# v2.net
KiCad netlist of a schematic drawn in EAGLE
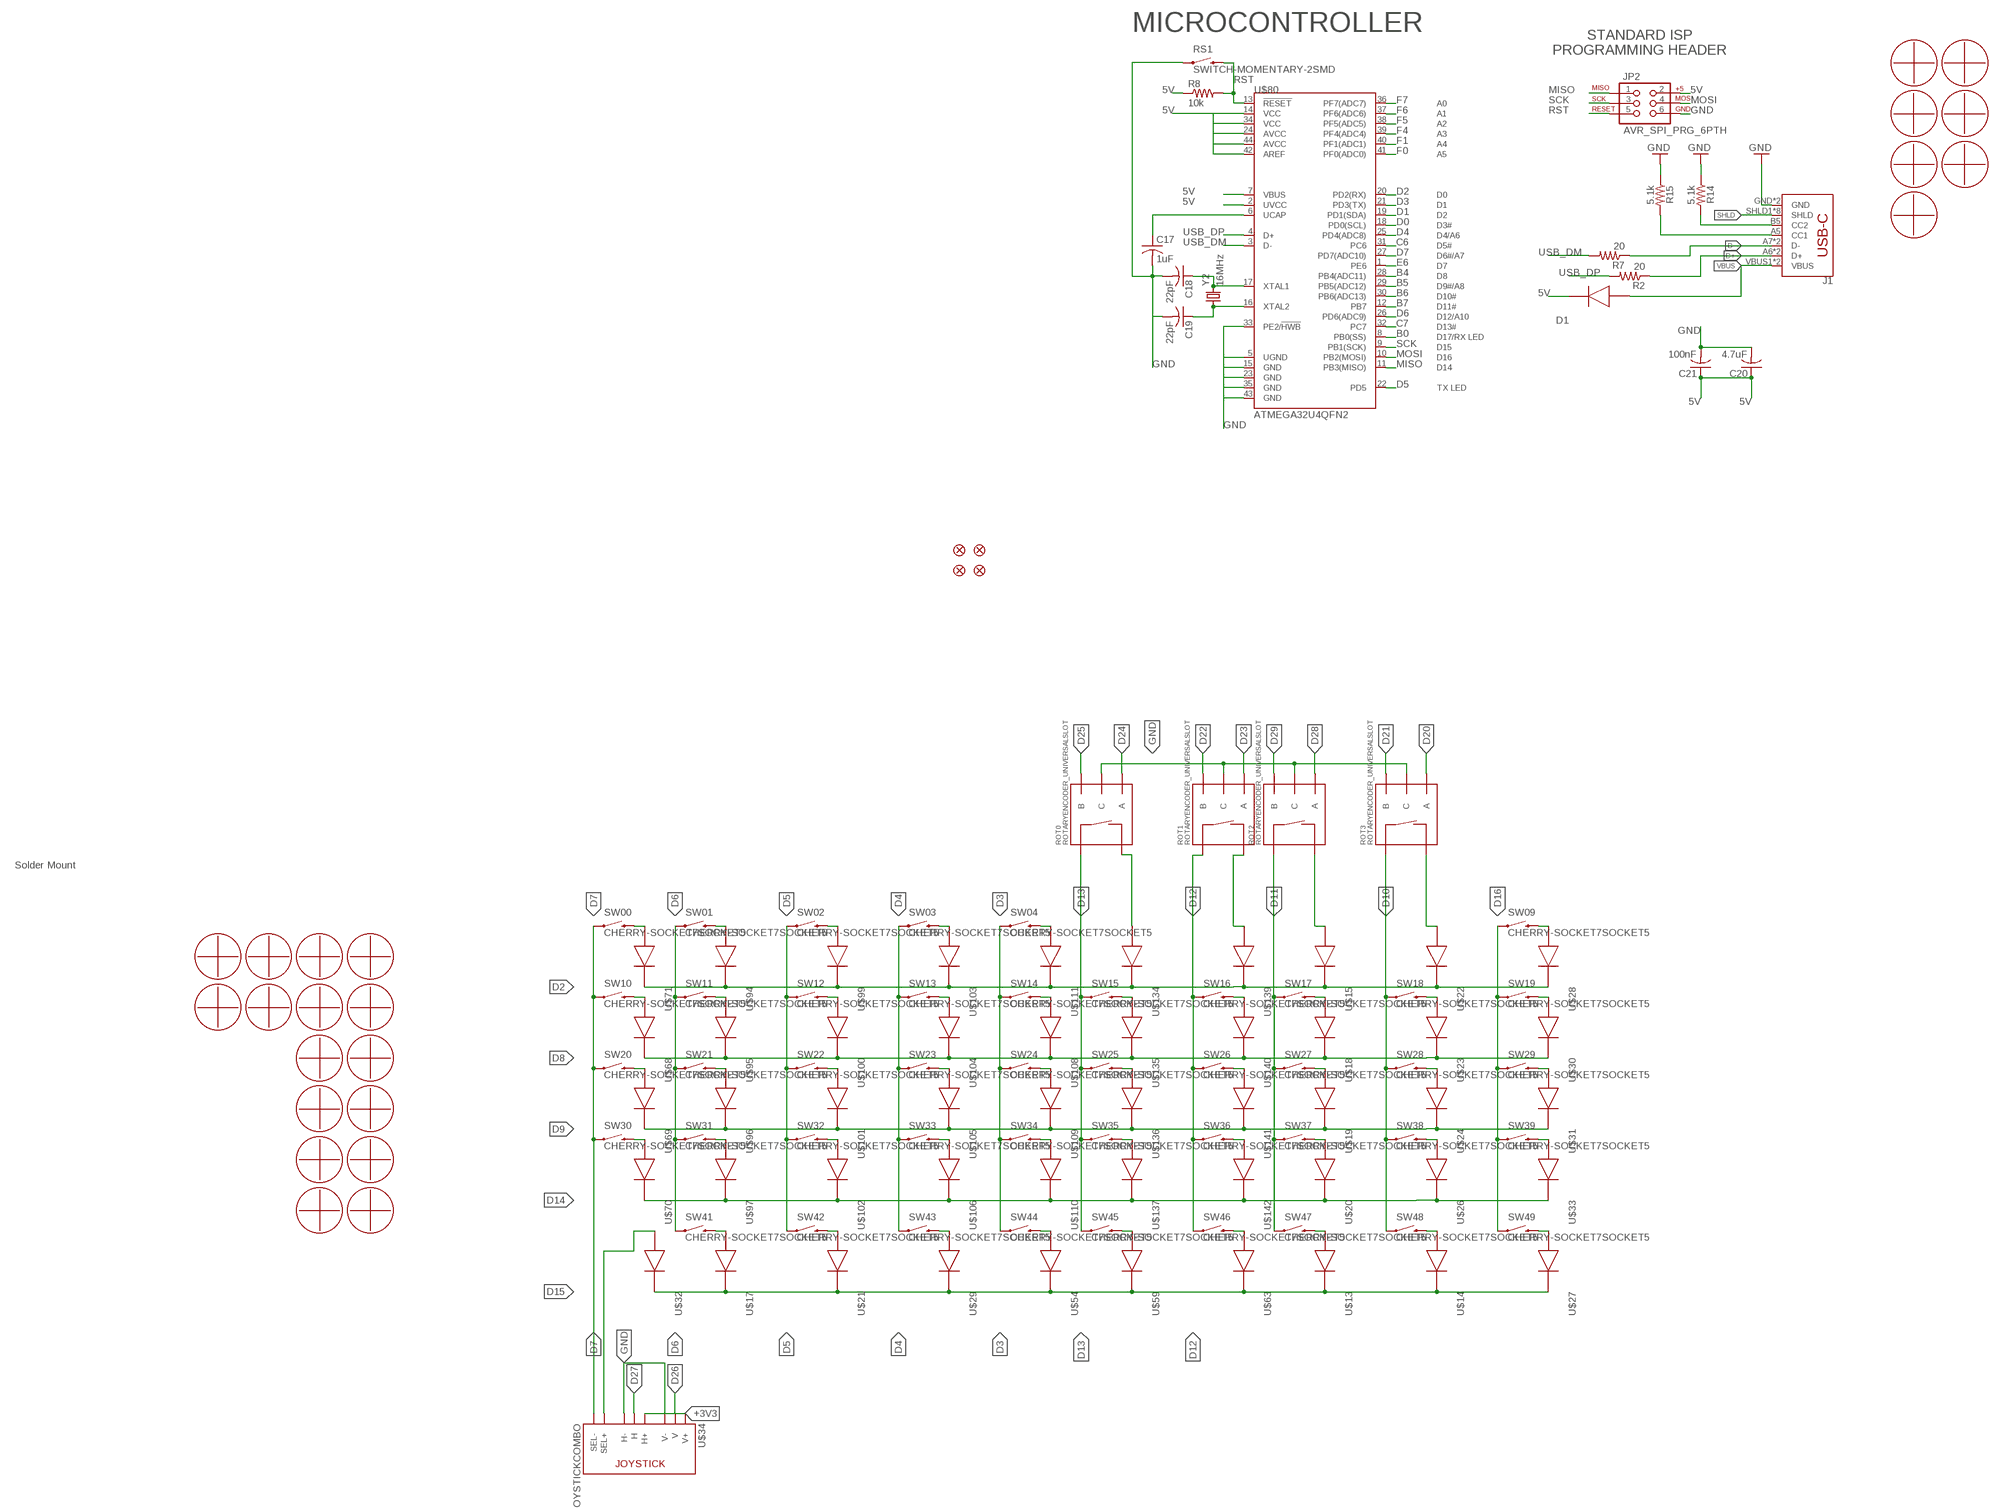
[diagram p0: schematic, sheet 1]

(export (version "E")
  (design (tool "Eeschema 10.0.6"))
  (components
    (comp (ref "C17")
      (value "1uF")
      (footprint "eagle-import:C0603")
      (libsource (lib "eagle-import") (part "C-USC0603"))
    )
    (comp (ref "C18")
      (value "22pF")
      (footprint "eagle-import:C0603")
      (libsource (lib "eagle-import") (part "C-USC0603"))
    )
    (comp (ref "C19")
      (value "22pF")
      (footprint "eagle-import:C0603")
      (libsource (lib "eagle-import") (part "C-USC0603"))
    )
    (comp (ref "C20")
      (value "4.7uF")
      (footprint "eagle-import:C0603")
      (libsource (lib "eagle-import") (part "C-USC0603"))
    )
    (comp (ref "C21")
      (value "100nF")
      (footprint "eagle-import:C0603")
      (libsource (lib "eagle-import") (part "C-USC0603"))
    )
    (comp (ref "D1")
      (value "SCHOTTKY")
      (footprint "eagle-import:SOD-123")
      (libsource (lib "eagle-import") (part "SCHOTTKY"))
    )
    (comp (ref "J1")
      (value "USB_C16PIN")
      (footprint "eagle-import:USB-C-16P")
      (libsource (lib "eagle-import") (part "USB_C16PIN"))
    )
    (comp (ref "JP2")
      (value "AVR_SPI_PRG_6PTH")
      (footprint "eagle-import:2X3")
      (libsource (lib "eagle-import") (part "AVR_SPI_PRG_6PTH"))
    )
    (comp (ref "R2")
      (value "20")
      (footprint "eagle-import:R0603")
      (libsource (lib "eagle-import") (part "R-US_R0603"))
    )
    (comp (ref "R7")
      (value "20")
      (footprint "eagle-import:R0603")
      (libsource (lib "eagle-import") (part "R-US_R0603"))
    )
    (comp (ref "R8")
      (value "10k")
      (footprint "eagle-import:R0603")
      (libsource (lib "eagle-import") (part "R-US_R0603"))
    )
    (comp (ref "R14")
      (value "5.1k")
      (footprint "eagle-import:0603")
      (libsource (lib "eagle-import") (part "5.1KOHM5.1KOHM-0603-1/10W-1%"))
    )
    (comp (ref "R15")
      (value "5.1k")
      (footprint "eagle-import:0603")
      (libsource (lib "eagle-import") (part "5.1KOHM5.1KOHM-0603-1/10W-1%"))
    )
    (comp (ref "ROT0")
      (value "ROTARYENCODER_UNIVERSALSLOT")
      (footprint "eagle-import:ROTARY_ENC_SLOT")
      (libsource (lib "eagle-import") (part "ROTARYENCODER_UNIVERSALSLOT"))
    )
    (comp (ref "ROT1")
      (value "ROTARYENCODER_UNIVERSALSLOT")
      (footprint "eagle-import:ROTARY_ENC_SLOT")
      (libsource (lib "eagle-import") (part "ROTARYENCODER_UNIVERSALSLOT"))
    )
    (comp (ref "ROT2")
      (value "ROTARYENCODER_UNIVERSALSLOT")
      (footprint "eagle-import:ROTARY_ENC_SLOT")
      (libsource (lib "eagle-import") (part "ROTARYENCODER_UNIVERSALSLOT"))
    )
    (comp (ref "ROT3")
      (value "ROTARYENCODER_UNIVERSALSLOT")
      (footprint "eagle-import:ROTARY_ENC_SLOT")
      (libsource (lib "eagle-import") (part "ROTARYENCODER_UNIVERSALSLOT"))
    )
    (comp (ref "RS1")
      (value "SWITCH-MOMENTARY-2SMD")
      (footprint "eagle-import:TACTILE_SWITCH_SMD")
      (libsource (lib "eagle-import") (part "SWITCH-MOMENTARY-2SMD"))
    )
    (comp (ref "SW00")
      (value "CHERRY-SOCKET7SOCKET5")
      (footprint "eagle-import:CHERRY-SOCKET5")
      (libsource (lib "eagle-import") (part "CHERRY-SOCKET7SOCKET5"))
    )
    (comp (ref "SW01")
      (value "CHERRY-SOCKET7SOCKET5")
      (footprint "eagle-import:CHERRY-SOCKET5")
      (libsource (lib "eagle-import") (part "CHERRY-SOCKET7SOCKET5"))
    )
    (comp (ref "SW02")
      (value "CHERRY-SOCKET7SOCKET5")
      (footprint "eagle-import:CHERRY-SOCKET5")
      (libsource (lib "eagle-import") (part "CHERRY-SOCKET7SOCKET5"))
    )
    (comp (ref "SW03")
      (value "CHERRY-SOCKET7SOCKET5")
      (footprint "eagle-import:CHERRY-SOCKET5")
      (libsource (lib "eagle-import") (part "CHERRY-SOCKET7SOCKET5"))
    )
    (comp (ref "SW04")
      (value "CHERRY-SOCKET7SOCKET5")
      (footprint "eagle-import:CHERRY-SOCKET5")
      (libsource (lib "eagle-import") (part "CHERRY-SOCKET7SOCKET5"))
    )
    (comp (ref "SW09")
      (value "CHERRY-SOCKET7SOCKET5")
      (footprint "eagle-import:CHERRY-SOCKET5")
      (libsource (lib "eagle-import") (part "CHERRY-SOCKET7SOCKET5"))
    )
    (comp (ref "SW10")
      (value "CHERRY-SOCKET7SOCKET5")
      (footprint "eagle-import:CHERRY-SOCKET5")
      (libsource (lib "eagle-import") (part "CHERRY-SOCKET7SOCKET5"))
    )
    (comp (ref "SW11")
      (value "CHERRY-SOCKET7SOCKET5")
      (footprint "eagle-import:CHERRY-SOCKET5")
      (libsource (lib "eagle-import") (part "CHERRY-SOCKET7SOCKET5"))
    )
    (comp (ref "SW12")
      (value "CHERRY-SOCKET7SOCKET5")
      (footprint "eagle-import:CHERRY-SOCKET5")
      (libsource (lib "eagle-import") (part "CHERRY-SOCKET7SOCKET5"))
    )
    (comp (ref "SW13")
      (value "CHERRY-SOCKET7SOCKET5")
      (footprint "eagle-import:CHERRY-SOCKET5")
      (libsource (lib "eagle-import") (part "CHERRY-SOCKET7SOCKET5"))
    )
    (comp (ref "SW14")
      (value "CHERRY-SOCKET7SOCKET5")
      (footprint "eagle-import:CHERRY-SOCKET5")
      (libsource (lib "eagle-import") (part "CHERRY-SOCKET7SOCKET5"))
    )
    (comp (ref "SW15")
      (value "CHERRY-SOCKET7SOCKET5")
      (footprint "eagle-import:CHERRY-SOCKET5")
      (libsource (lib "eagle-import") (part "CHERRY-SOCKET7SOCKET5"))
    )
    (comp (ref "SW16")
      (value "CHERRY-SOCKET7SOCKET5")
      (footprint "eagle-import:CHERRY-SOCKET5")
      (libsource (lib "eagle-import") (part "CHERRY-SOCKET7SOCKET5"))
    )
    (comp (ref "SW17")
      (value "CHERRY-SOCKET7SOCKET5")
      (footprint "eagle-import:CHERRY-SOCKET5")
      (libsource (lib "eagle-import") (part "CHERRY-SOCKET7SOCKET5"))
    )
    (comp (ref "SW18")
      (value "CHERRY-SOCKET7SOCKET5")
      (footprint "eagle-import:CHERRY-SOCKET5")
      (libsource (lib "eagle-import") (part "CHERRY-SOCKET7SOCKET5"))
    )
    (comp (ref "SW19")
      (value "CHERRY-SOCKET7SOCKET5")
      (footprint "eagle-import:CHERRY-SOCKET5")
      (libsource (lib "eagle-import") (part "CHERRY-SOCKET7SOCKET5"))
    )
    (comp (ref "SW20")
      (value "CHERRY-SOCKET7SOCKET5")
      (footprint "eagle-import:CHERRY-SOCKET5")
      (libsource (lib "eagle-import") (part "CHERRY-SOCKET7SOCKET5"))
    )
    (comp (ref "SW21")
      (value "CHERRY-SOCKET7SOCKET5")
      (footprint "eagle-import:CHERRY-SOCKET5")
      (libsource (lib "eagle-import") (part "CHERRY-SOCKET7SOCKET5"))
    )
    (comp (ref "SW22")
      (value "CHERRY-SOCKET7SOCKET5")
      (footprint "eagle-import:CHERRY-SOCKET5")
      (libsource (lib "eagle-import") (part "CHERRY-SOCKET7SOCKET5"))
    )
    (comp (ref "SW23")
      (value "CHERRY-SOCKET7SOCKET5")
      (footprint "eagle-import:CHERRY-SOCKET5")
      (libsource (lib "eagle-import") (part "CHERRY-SOCKET7SOCKET5"))
    )
    (comp (ref "SW24")
      (value "CHERRY-SOCKET7SOCKET5")
      (footprint "eagle-import:CHERRY-SOCKET5")
      (libsource (lib "eagle-import") (part "CHERRY-SOCKET7SOCKET5"))
    )
    (comp (ref "SW25")
      (value "CHERRY-SOCKET7SOCKET5")
      (footprint "eagle-import:CHERRY-SOCKET5")
      (libsource (lib "eagle-import") (part "CHERRY-SOCKET7SOCKET5"))
    )
    (comp (ref "SW26")
      (value "CHERRY-SOCKET7SOCKET5")
      (footprint "eagle-import:CHERRY-SOCKET5")
      (libsource (lib "eagle-import") (part "CHERRY-SOCKET7SOCKET5"))
    )
    (comp (ref "SW27")
      (value "CHERRY-SOCKET7SOCKET5")
      (footprint "eagle-import:CHERRY-SOCKET5")
      (libsource (lib "eagle-import") (part "CHERRY-SOCKET7SOCKET5"))
    )
    (comp (ref "SW28")
      (value "CHERRY-SOCKET7SOCKET5")
      (footprint "eagle-import:CHERRY-SOCKET5")
      (libsource (lib "eagle-import") (part "CHERRY-SOCKET7SOCKET5"))
    )
    (comp (ref "SW29")
      (value "CHERRY-SOCKET7SOCKET5")
      (footprint "eagle-import:CHERRY-SOCKET5")
      (libsource (lib "eagle-import") (part "CHERRY-SOCKET7SOCKET5"))
    )
    (comp (ref "SW30")
      (value "CHERRY-SOCKET7SOCKET5")
      (footprint "eagle-import:CHERRY-SOCKET5")
      (libsource (lib "eagle-import") (part "CHERRY-SOCKET7SOCKET5"))
    )
    (comp (ref "SW31")
      (value "CHERRY-SOCKET7SOCKET5")
      (footprint "eagle-import:CHERRY-SOCKET5")
      (libsource (lib "eagle-import") (part "CHERRY-SOCKET7SOCKET5"))
    )
    (comp (ref "SW32")
      (value "CHERRY-SOCKET7SOCKET5")
      (footprint "eagle-import:CHERRY-SOCKET5")
      (libsource (lib "eagle-import") (part "CHERRY-SOCKET7SOCKET5"))
    )
    (comp (ref "SW33")
      (value "CHERRY-SOCKET7SOCKET5")
      (footprint "eagle-import:CHERRY-SOCKET5")
      (libsource (lib "eagle-import") (part "CHERRY-SOCKET7SOCKET5"))
    )
    (comp (ref "SW34")
      (value "CHERRY-SOCKET7SOCKET5")
      (footprint "eagle-import:CHERRY-SOCKET5")
      (libsource (lib "eagle-import") (part "CHERRY-SOCKET7SOCKET5"))
    )
    (comp (ref "SW35")
      (value "CHERRY-SOCKET7SOCKET5")
      (footprint "eagle-import:CHERRY-SOCKET5")
      (libsource (lib "eagle-import") (part "CHERRY-SOCKET7SOCKET5"))
    )
    (comp (ref "SW36")
      (value "CHERRY-SOCKET7SOCKET5")
      (footprint "eagle-import:CHERRY-SOCKET5")
      (libsource (lib "eagle-import") (part "CHERRY-SOCKET7SOCKET5"))
    )
    (comp (ref "SW37")
      (value "CHERRY-SOCKET7SOCKET5")
      (footprint "eagle-import:CHERRY-SOCKET5")
      (libsource (lib "eagle-import") (part "CHERRY-SOCKET7SOCKET5"))
    )
    (comp (ref "SW38")
      (value "CHERRY-SOCKET7SOCKET5")
      (footprint "eagle-import:CHERRY-SOCKET5")
      (libsource (lib "eagle-import") (part "CHERRY-SOCKET7SOCKET5"))
    )
    (comp (ref "SW39")
      (value "CHERRY-SOCKET7SOCKET5")
      (footprint "eagle-import:CHERRY-SOCKET5")
      (libsource (lib "eagle-import") (part "CHERRY-SOCKET7SOCKET5"))
    )
    (comp (ref "SW41")
      (value "CHERRY-SOCKET7SOCKET5")
      (footprint "eagle-import:CHERRY-SOCKET5")
      (libsource (lib "eagle-import") (part "CHERRY-SOCKET7SOCKET5"))
    )
    (comp (ref "SW42")
      (value "CHERRY-SOCKET7SOCKET5")
      (footprint "eagle-import:CHERRY-SOCKET5")
      (libsource (lib "eagle-import") (part "CHERRY-SOCKET7SOCKET5"))
    )
    (comp (ref "SW43")
      (value "CHERRY-SOCKET7SOCKET5")
      (footprint "eagle-import:CHERRY-SOCKET5")
      (libsource (lib "eagle-import") (part "CHERRY-SOCKET7SOCKET5"))
    )
    (comp (ref "SW44")
      (value "CHERRY-SOCKET7SOCKET5")
      (footprint "eagle-import:CHERRY-SOCKET5")
      (libsource (lib "eagle-import") (part "CHERRY-SOCKET7SOCKET5"))
    )
    (comp (ref "SW45")
      (value "CHERRY-SOCKET7SOCKET5")
      (footprint "eagle-import:CHERRY-SOCKET5")
      (libsource (lib "eagle-import") (part "CHERRY-SOCKET7SOCKET5"))
    )
    (comp (ref "SW46")
      (value "CHERRY-SOCKET7SOCKET5")
      (footprint "eagle-import:CHERRY-SOCKET5")
      (libsource (lib "eagle-import") (part "CHERRY-SOCKET7SOCKET5"))
    )
    (comp (ref "SW47")
      (value "CHERRY-SOCKET7SOCKET5")
      (footprint "eagle-import:CHERRY-SOCKET5")
      (libsource (lib "eagle-import") (part "CHERRY-SOCKET7SOCKET5"))
    )
    (comp (ref "SW48")
      (value "CHERRY-SOCKET7SOCKET5")
      (footprint "eagle-import:CHERRY-SOCKET5")
      (libsource (lib "eagle-import") (part "CHERRY-SOCKET7SOCKET5"))
    )
    (comp (ref "SW49")
      (value "CHERRY-SOCKET7SOCKET5")
      (footprint "eagle-import:CHERRY-SOCKET5")
      (libsource (lib "eagle-import") (part "CHERRY-SOCKET7SOCKET5"))
    )
    (comp (ref "U$1")
      (value "M2MOUNT")
      (footprint "eagle-import:M2MOUNT")
      (libsource (lib "eagle-import") (part "M2MOUNT"))
    )
    (comp (ref "U$2")
      (value "M2MOUNT")
      (footprint "eagle-import:M2MOUNT")
      (libsource (lib "eagle-import") (part "M2MOUNT"))
    )
    (comp (ref "U$3")
      (value "M2MOUNT")
      (footprint "eagle-import:M2MOUNT")
      (libsource (lib "eagle-import") (part "M2MOUNT"))
    )
    (comp (ref "U$4")
      (value "M2MOUNT")
      (footprint "eagle-import:M2MOUNT")
      (libsource (lib "eagle-import") (part "M2MOUNT"))
    )
    (comp (ref "U$5")
      (value "M2MOUNT")
      (footprint "eagle-import:M2MOUNT")
      (libsource (lib "eagle-import") (part "M2MOUNT"))
    )
    (comp (ref "U$6")
      (value "M2MOUNT")
      (footprint "eagle-import:M2MOUNT")
      (libsource (lib "eagle-import") (part "M2MOUNT"))
    )
    (comp (ref "U$7")
      (value "M2MOUNT")
      (footprint "eagle-import:M2MOUNT")
      (libsource (lib "eagle-import") (part "M2MOUNT"))
    )
    (comp (ref "U$8")
      (value "M2MOUNT")
      (footprint "eagle-import:M2MOUNT")
      (libsource (lib "eagle-import") (part "M2MOUNT"))
    )
    (comp (ref "U$9")
      (value "M2MOUNT")
      (footprint "eagle-import:M2MOUNT")
      (libsource (lib "eagle-import") (part "M2MOUNT"))
    )
    (comp (ref "U$10")
      (value "M2MOUNT")
      (footprint "eagle-import:M2MOUNT")
      (libsource (lib "eagle-import") (part "M2MOUNT"))
    )
    (comp (ref "U$11")
      (value "M2MOUNT")
      (footprint "eagle-import:M2MOUNT")
      (libsource (lib "eagle-import") (part "M2MOUNT"))
    )
    (comp (ref "U$12")
      (value "M2MOUNT")
      (footprint "eagle-import:M2MOUNT")
      (libsource (lib "eagle-import") (part "M2MOUNT"))
    )
    (comp (ref "U$13")
      (value "1N4148WS")
      (footprint "eagle-import:SOD-323SLIM")
      (libsource (lib "eagle-import") (part "1N4148WS"))
    )
    (comp (ref "U$14")
      (value "1N4148WS")
      (footprint "eagle-import:SOD-323SLIM")
      (libsource (lib "eagle-import") (part "1N4148WS"))
    )
    (comp (ref "U$15")
      (value "1N4148WS")
      (footprint "eagle-import:SOD-323SLIM")
      (libsource (lib "eagle-import") (part "1N4148WS"))
    )
    (comp (ref "U$16")
      (value "M2MOUNT")
      (footprint "eagle-import:M2MOUNT")
      (libsource (lib "eagle-import") (part "M2MOUNT"))
    )
    (comp (ref "U$17")
      (value "1N4148WS")
      (footprint "eagle-import:SOD-323SLIM")
      (libsource (lib "eagle-import") (part "1N4148WS"))
    )
    (comp (ref "U$18")
      (value "1N4148WS")
      (footprint "eagle-import:SOD-323SLIM")
      (libsource (lib "eagle-import") (part "1N4148WS"))
    )
    (comp (ref "U$19")
      (value "1N4148WS")
      (footprint "eagle-import:SOD-323SLIM")
      (libsource (lib "eagle-import") (part "1N4148WS"))
    )
    (comp (ref "U$20")
      (value "1N4148WS")
      (footprint "eagle-import:SOD-323SLIM")
      (libsource (lib "eagle-import") (part "1N4148WS"))
    )
    (comp (ref "U$21")
      (value "1N4148WS")
      (footprint "eagle-import:SOD-323SLIM")
      (libsource (lib "eagle-import") (part "1N4148WS"))
    )
    (comp (ref "U$22")
      (value "1N4148WS")
      (footprint "eagle-import:SOD-323SLIM")
      (libsource (lib "eagle-import") (part "1N4148WS"))
    )
    (comp (ref "U$23")
      (value "1N4148WS")
      (footprint "eagle-import:SOD-323SLIM")
      (libsource (lib "eagle-import") (part "1N4148WS"))
    )
    (comp (ref "U$24")
      (value "1N4148WS")
      (footprint "eagle-import:SOD-323SLIM")
      (libsource (lib "eagle-import") (part "1N4148WS"))
    )
    (comp (ref "U$25")
      (value "M2MOUNT")
      (footprint "eagle-import:M2MOUNT")
      (libsource (lib "eagle-import") (part "M2MOUNT"))
    )
    (comp (ref "U$26")
      (value "1N4148WS")
      (footprint "eagle-import:SOD-323SLIM")
      (libsource (lib "eagle-import") (part "1N4148WS"))
    )
    (comp (ref "U$27")
      (value "1N4148WS")
      (footprint "eagle-import:SOD-323SLIM")
      (libsource (lib "eagle-import") (part "1N4148WS"))
    )
    (comp (ref "U$28")
      (value "1N4148WS")
      (footprint "eagle-import:SOD-323SLIM")
      (libsource (lib "eagle-import") (part "1N4148WS"))
    )
    (comp (ref "U$29")
      (value "1N4148WS")
      (footprint "eagle-import:SOD-323SLIM")
      (libsource (lib "eagle-import") (part "1N4148WS"))
    )
    (comp (ref "U$30")
      (value "1N4148WS")
      (footprint "eagle-import:SOD-323SLIM")
      (libsource (lib "eagle-import") (part "1N4148WS"))
    )
    (comp (ref "U$31")
      (value "1N4148WS")
      (footprint "eagle-import:SOD-323SLIM")
      (libsource (lib "eagle-import") (part "1N4148WS"))
    )
    (comp (ref "U$32")
      (value "1N4148WS")
      (footprint "eagle-import:SOD-323SLIM")
      (libsource (lib "eagle-import") (part "1N4148WS"))
    )
    (comp (ref "U$33")
      (value "1N4148WS")
      (footprint "eagle-import:SOD-323SLIM")
      (libsource (lib "eagle-import") (part "1N4148WS"))
    )
    (comp (ref "U$34")
      (value "JOYSTICKCOMBO")
      (footprint "eagle-import:JOYSTICKCOMBO")
      (libsource (lib "eagle-import") (part "JOYSTICKCOMBO"))
    )
    (comp (ref "U$35")
      (value "M2MOUNT3.65HOLE")
      (footprint "eagle-import:M2SOLDERC2916348")
      (libsource (lib "eagle-import") (part "M2MOUNT3.65HOLE"))
    )
    (comp (ref "U$36")
      (value "M2MOUNT3.65HOLE")
      (footprint "eagle-import:M2SOLDERC2916348")
      (libsource (lib "eagle-import") (part "M2MOUNT3.65HOLE"))
    )
    (comp (ref "U$37")
      (value "M2MOUNT3.65HOLE")
      (footprint "eagle-import:M2SOLDERC2916348")
      (libsource (lib "eagle-import") (part "M2MOUNT3.65HOLE"))
    )
    (comp (ref "U$38")
      (value "FIDUCIAL_1MM")
      (footprint "eagle-import:FIDUCIAL_1MM")
      (libsource (lib "eagle-import") (part "FIDUCIAL_1MM"))
    )
    (comp (ref "U$39")
      (value "FIDUCIAL_1MM")
      (footprint "eagle-import:FIDUCIAL_1MM")
      (libsource (lib "eagle-import") (part "FIDUCIAL_1MM"))
    )
    (comp (ref "U$40")
      (value "M2MOUNT3.65HOLE")
      (footprint "eagle-import:M2SOLDERC2916348")
      (libsource (lib "eagle-import") (part "M2MOUNT3.65HOLE"))
    )
    (comp (ref "U$41")
      (value "M2MOUNT3.65HOLE")
      (footprint "eagle-import:M2SOLDERC2916348")
      (libsource (lib "eagle-import") (part "M2MOUNT3.65HOLE"))
    )
    (comp (ref "U$42")
      (value "M2MOUNT3.65HOLE")
      (footprint "eagle-import:M2SOLDERC2916348")
      (libsource (lib "eagle-import") (part "M2MOUNT3.65HOLE"))
    )
    (comp (ref "U$43")
      (value "M2MOUNT3.65HOLE")
      (footprint "eagle-import:M2SOLDERC2916348")
      (libsource (lib "eagle-import") (part "M2MOUNT3.65HOLE"))
    )
    (comp (ref "U$44")
      (value "M2MOUNT")
      (footprint "eagle-import:M2MOUNT")
      (libsource (lib "eagle-import") (part "M2MOUNT"))
    )
    (comp (ref "U$45")
      (value "M2MOUNT")
      (footprint "eagle-import:M2MOUNT")
      (libsource (lib "eagle-import") (part "M2MOUNT"))
    )
    (comp (ref "U$54")
      (value "1N4148WS")
      (footprint "eagle-import:SOD-323SLIM")
      (libsource (lib "eagle-import") (part "1N4148WS"))
    )
    (comp (ref "U$59")
      (value "1N4148WS")
      (footprint "eagle-import:SOD-323SLIM")
      (libsource (lib "eagle-import") (part "1N4148WS"))
    )
    (comp (ref "U$62")
      (value "FIDUCIAL_1MM")
      (footprint "eagle-import:FIDUCIAL_1MM")
      (libsource (lib "eagle-import") (part "FIDUCIAL_1MM"))
    )
    (comp (ref "U$63")
      (value "1N4148WS")
      (footprint "eagle-import:SOD-323SLIM")
      (libsource (lib "eagle-import") (part "1N4148WS"))
    )
    (comp (ref "U$64")
      (value "FIDUCIAL_1MM")
      (footprint "eagle-import:FIDUCIAL_1MM")
      (libsource (lib "eagle-import") (part "FIDUCIAL_1MM"))
    )
    (comp (ref "U$68")
      (value "1N4148WS")
      (footprint "eagle-import:SOD-323SLIM")
      (libsource (lib "eagle-import") (part "1N4148WS"))
    )
    (comp (ref "U$69")
      (value "1N4148WS")
      (footprint "eagle-import:SOD-323SLIM")
      (libsource (lib "eagle-import") (part "1N4148WS"))
    )
    (comp (ref "U$70")
      (value "1N4148WS")
      (footprint "eagle-import:SOD-323SLIM")
      (libsource (lib "eagle-import") (part "1N4148WS"))
    )
    (comp (ref "U$71")
      (value "1N4148WS")
      (footprint "eagle-import:SOD-323SLIM")
      (libsource (lib "eagle-import") (part "1N4148WS"))
    )
    (comp (ref "U$80")
      (value "ATMEGA32U4QFN2")
      (footprint "eagle-import:QFN-44-NOPAD")
      (libsource (lib "eagle-import") (part "ATMEGA32U4QFN2"))
    )
    (comp (ref "U$94")
      (value "1N4148WS")
      (footprint "eagle-import:SOD-323SLIM")
      (libsource (lib "eagle-import") (part "1N4148WS"))
    )
    (comp (ref "U$95")
      (value "1N4148WS")
      (footprint "eagle-import:SOD-323SLIM")
      (libsource (lib "eagle-import") (part "1N4148WS"))
    )
    (comp (ref "U$96")
      (value "1N4148WS")
      (footprint "eagle-import:SOD-323SLIM")
      (libsource (lib "eagle-import") (part "1N4148WS"))
    )
    (comp (ref "U$97")
      (value "1N4148WS")
      (footprint "eagle-import:SOD-323SLIM")
      (libsource (lib "eagle-import") (part "1N4148WS"))
    )
    (comp (ref "U$99")
      (value "1N4148WS")
      (footprint "eagle-import:SOD-323SLIM")
      (libsource (lib "eagle-import") (part "1N4148WS"))
    )
    (comp (ref "U$100")
      (value "1N4148WS")
      (footprint "eagle-import:SOD-323SLIM")
      (libsource (lib "eagle-import") (part "1N4148WS"))
    )
    (comp (ref "U$101")
      (value "1N4148WS")
      (footprint "eagle-import:SOD-323SLIM")
      (libsource (lib "eagle-import") (part "1N4148WS"))
    )
    (comp (ref "U$102")
      (value "1N4148WS")
      (footprint "eagle-import:SOD-323SLIM")
      (libsource (lib "eagle-import") (part "1N4148WS"))
    )
    (comp (ref "U$103")
      (value "1N4148WS")
      (footprint "eagle-import:SOD-323SLIM")
      (libsource (lib "eagle-import") (part "1N4148WS"))
    )
    (comp (ref "U$104")
      (value "1N4148WS")
      (footprint "eagle-import:SOD-323SLIM")
      (libsource (lib "eagle-import") (part "1N4148WS"))
    )
    (comp (ref "U$105")
      (value "1N4148WS")
      (footprint "eagle-import:SOD-323SLIM")
      (libsource (lib "eagle-import") (part "1N4148WS"))
    )
    (comp (ref "U$106")
      (value "1N4148WS")
      (footprint "eagle-import:SOD-323SLIM")
      (libsource (lib "eagle-import") (part "1N4148WS"))
    )
    (comp (ref "U$108")
      (value "1N4148WS")
      (footprint "eagle-import:SOD-323SLIM")
      (libsource (lib "eagle-import") (part "1N4148WS"))
    )
    (comp (ref "U$109")
      (value "1N4148WS")
      (footprint "eagle-import:SOD-323SLIM")
      (libsource (lib "eagle-import") (part "1N4148WS"))
    )
    (comp (ref "U$110")
      (value "1N4148WS")
      (footprint "eagle-import:SOD-323SLIM")
      (libsource (lib "eagle-import") (part "1N4148WS"))
    )
    (comp (ref "U$111")
      (value "1N4148WS")
      (footprint "eagle-import:SOD-323SLIM")
      (libsource (lib "eagle-import") (part "1N4148WS"))
    )
    (comp (ref "U$134")
      (value "1N4148WS")
      (footprint "eagle-import:SOD-323SLIM")
      (libsource (lib "eagle-import") (part "1N4148WS"))
    )
    (comp (ref "U$135")
      (value "1N4148WS")
      (footprint "eagle-import:SOD-323SLIM")
      (libsource (lib "eagle-import") (part "1N4148WS"))
    )
    (comp (ref "U$136")
      (value "1N4148WS")
      (footprint "eagle-import:SOD-323SLIM")
      (libsource (lib "eagle-import") (part "1N4148WS"))
    )
    (comp (ref "U$137")
      (value "1N4148WS")
      (footprint "eagle-import:SOD-323SLIM")
      (libsource (lib "eagle-import") (part "1N4148WS"))
    )
    (comp (ref "U$139")
      (value "1N4148WS")
      (footprint "eagle-import:SOD-323SLIM")
      (libsource (lib "eagle-import") (part "1N4148WS"))
    )
    (comp (ref "U$140")
      (value "1N4148WS")
      (footprint "eagle-import:SOD-323SLIM")
      (libsource (lib "eagle-import") (part "1N4148WS"))
    )
    (comp (ref "U$141")
      (value "1N4148WS")
      (footprint "eagle-import:SOD-323SLIM")
      (libsource (lib "eagle-import") (part "1N4148WS"))
    )
    (comp (ref "U$142")
      (value "1N4148WS")
      (footprint "eagle-import:SOD-323SLIM")
      (libsource (lib "eagle-import") (part "1N4148WS"))
    )
    (comp (ref "Y2")
      (value "16MHz")
      (footprint "eagle-import:RESONATOR3225")
      (libsource (lib "eagle-import") (part "CRYSTAL"))
    )
  )
  (nets
    (net (code "1") (name "+3V3") (class "Default")
      (node (ref "U$34") (pin "H1") (pinfunction "H+_H1") (pintype "bidirectional"))
      (node (ref "U$34") (pin "HS1") (pinfunction "H+_HS1") (pintype "bidirectional"))
      (node (ref "U$34") (pin "V1") (pinfunction "V+_V1") (pintype "bidirectional"))
      (node (ref "U$34") (pin "VS1") (pinfunction "V+_VS1") (pintype "bidirectional"))
    )
    (net (code "2") (name "/5V") (class "Default")
      (node (ref "C20") (pin "1") (pinfunction "1_1") (pintype "passive"))
      (node (ref "C21") (pin "1") (pinfunction "1_1") (pintype "passive"))
      (node (ref "D1") (pin "CAT") (pinfunction "CAT_CAT") (pintype "bidirectional"))
      (node (ref "JP2") (pin "2") (pinfunction "2_2") (pintype "passive"))
      (node (ref "R8") (pin "1") (pinfunction "1_1") (pintype "passive"))
      (node (ref "U$80") (pin "14") (pinfunction "VCC_14") (pintype "bidirectional"))
      (node (ref "U$80") (pin "2") (pinfunction "UVCC_2") (pintype "bidirectional"))
      (node (ref "U$80") (pin "24") (pinfunction "AVCC_24") (pintype "bidirectional"))
      (node (ref "U$80") (pin "34") (pinfunction "VCC_34") (pintype "bidirectional"))
      (node (ref "U$80") (pin "42") (pinfunction "AREF_42") (pintype "bidirectional"))
      (node (ref "U$80") (pin "44") (pinfunction "AVCC_44") (pintype "bidirectional"))
      (node (ref "U$80") (pin "7") (pinfunction "VBUS_7") (pintype "bidirectional"))
    )
    (net (code "3") (name "/B0") (class "Default")
      (node (ref "U$80") (pin "8") (pinfunction "PB0(SS)_8") (pintype "bidirectional"))
    )
    (net (code "4") (name "/B4") (class "Default")
      (node (ref "U$80") (pin "28") (pinfunction "PB4(ADC11)_28") (pintype "bidirectional"))
    )
    (net (code "5") (name "/B5") (class "Default")
      (node (ref "U$80") (pin "29") (pinfunction "PB5(ADC12)_29") (pintype "bidirectional"))
    )
    (net (code "6") (name "/B6") (class "Default")
      (node (ref "U$80") (pin "30") (pinfunction "PB6(ADC13)_30") (pintype "bidirectional"))
    )
    (net (code "7") (name "/B7") (class "Default")
      (node (ref "U$80") (pin "12") (pinfunction "PB7_12") (pintype "bidirectional"))
    )
    (net (code "8") (name "/C6") (class "Default")
      (node (ref "U$80") (pin "31") (pinfunction "PC6_31") (pintype "bidirectional"))
    )
    (net (code "9") (name "/C7") (class "Default")
      (node (ref "U$80") (pin "32") (pinfunction "PC7_32") (pintype "bidirectional"))
    )
    (net (code "10") (name "/D0") (class "Default")
      (node (ref "U$80") (pin "18") (pinfunction "PD0(SCL)_18") (pintype "bidirectional"))
    )
    (net (code "11") (name "/D1") (class "Default")
      (node (ref "U$80") (pin "19") (pinfunction "PD1(SDA)_19") (pintype "bidirectional"))
    )
    (net (code "12") (name "/E6") (class "Default")
      (node (ref "U$80") (pin "1") (pinfunction "PE6_1") (pintype "bidirectional"))
    )
    (net (code "13") (name "/F0") (class "Default")
      (node (ref "U$80") (pin "41") (pinfunction "PF0(ADC0)_41") (pintype "bidirectional"))
    )
    (net (code "14") (name "/F1") (class "Default")
      (node (ref "U$80") (pin "40") (pinfunction "PF1(ADC1)_40") (pintype "bidirectional"))
    )
    (net (code "15") (name "/F4") (class "Default")
      (node (ref "U$80") (pin "39") (pinfunction "PF4(ADC4)_39") (pintype "bidirectional"))
    )
    (net (code "16") (name "/F5") (class "Default")
      (node (ref "U$80") (pin "38") (pinfunction "PF5(ADC5)_38") (pintype "bidirectional"))
    )
    (net (code "17") (name "/F6") (class "Default")
      (node (ref "U$80") (pin "37") (pinfunction "PF6(ADC6)_37") (pintype "bidirectional"))
    )
    (net (code "18") (name "/F7") (class "Default")
      (node (ref "U$80") (pin "36") (pinfunction "PF7(ADC7)_36") (pintype "bidirectional"))
    )
    (net (code "19") (name "/MISO") (class "Default")
      (node (ref "JP2") (pin "1") (pinfunction "1_1") (pintype "passive"))
      (node (ref "U$80") (pin "11") (pinfunction "PB3(MISO)_11") (pintype "bidirectional"))
    )
    (net (code "20") (name "/MOSI") (class "Default")
      (node (ref "JP2") (pin "4") (pinfunction "4_4") (pintype "passive"))
      (node (ref "U$80") (pin "10") (pinfunction "PB2(MOSI)_10") (pintype "bidirectional"))
    )
    (net (code "21") (name "/RST") (class "Default")
      (node (ref "JP2") (pin "5") (pinfunction "5_5") (pintype "passive"))
      (node (ref "R8") (pin "2") (pinfunction "2_2") (pintype "passive"))
      (node (ref "RS1") (pin "3") (pinfunction "2_3") (pintype "passive"))
      (node (ref "U$80") (pin "13") (pinfunction "~{RESET}_13") (pintype "bidirectional"))
    )
    (net (code "22") (name "/SCK") (class "Default")
      (node (ref "JP2") (pin "3") (pinfunction "3_3") (pintype "passive"))
      (node (ref "U$80") (pin "9") (pinfunction "PB1(SCK)_9") (pintype "bidirectional"))
    )
    (net (code "23") (name "/USB_DM") (class "Default")
      (node (ref "R7") (pin "2") (pinfunction "2_2") (pintype "passive"))
      (node (ref "U$80") (pin "3") (pinfunction "D-_3") (pintype "bidirectional"))
    )
    (net (code "24") (name "/USB_DP") (class "Default")
      (node (ref "R2") (pin "2") (pinfunction "2_2") (pintype "passive"))
      (node (ref "U$80") (pin "4") (pinfunction "D+_4") (pintype "bidirectional"))
    )
    (net (code "25") (name "D+") (class "Default")
      (node (ref "J1") (pin "A6") (pinfunction "D+_A6") (pintype "bidirectional"))
      (node (ref "J1") (pin "B6") (pinfunction "D+_B6") (pintype "bidirectional"))
      (node (ref "R2") (pin "1") (pinfunction "1_1") (pintype "passive"))
    )
    (net (code "26") (name "D-") (class "Default")
      (node (ref "J1") (pin "A7") (pinfunction "D-_A7") (pintype "bidirectional"))
      (node (ref "J1") (pin "B7") (pinfunction "D-_B7") (pintype "bidirectional"))
      (node (ref "R7") (pin "1") (pinfunction "1_1") (pintype "passive"))
    )
    (net (code "27") (name "D2") (class "Default")
      (node (ref "U$103") (pin "GND") (pinfunction "CAT_GND") (pintype "bidirectional"))
      (node (ref "U$111") (pin "GND") (pinfunction "CAT_GND") (pintype "bidirectional"))
      (node (ref "U$134") (pin "GND") (pinfunction "CAT_GND") (pintype "bidirectional"))
      (node (ref "U$139") (pin "GND") (pinfunction "CAT_GND") (pintype "bidirectional"))
      (node (ref "U$15") (pin "GND") (pinfunction "CAT_GND") (pintype "bidirectional"))
      (node (ref "U$22") (pin "GND") (pinfunction "CAT_GND") (pintype "bidirectional"))
      (node (ref "U$28") (pin "GND") (pinfunction "CAT_GND") (pintype "bidirectional"))
      (node (ref "U$71") (pin "GND") (pinfunction "CAT_GND") (pintype "bidirectional"))
      (node (ref "U$80") (pin "20") (pinfunction "PD2(RX)_20") (pintype "bidirectional"))
      (node (ref "U$94") (pin "GND") (pinfunction "CAT_GND") (pintype "bidirectional"))
      (node (ref "U$99") (pin "GND") (pinfunction "CAT_GND") (pintype "bidirectional"))
    )
    (net (code "28") (name "D3") (class "Default")
      (node (ref "SW04") (pin "A") (pinfunction "1_A") (pintype "passive"))
      (node (ref "SW14") (pin "A") (pinfunction "1_A") (pintype "passive"))
      (node (ref "SW24") (pin "A") (pinfunction "1_A") (pintype "passive"))
      (node (ref "SW34") (pin "A") (pinfunction "1_A") (pintype "passive"))
      (node (ref "SW44") (pin "A") (pinfunction "1_A") (pintype "passive"))
      (node (ref "U$80") (pin "21") (pinfunction "PD3(TX)_21") (pintype "bidirectional"))
    )
    (net (code "29") (name "D4") (class "Default")
      (node (ref "SW03") (pin "A") (pinfunction "1_A") (pintype "passive"))
      (node (ref "SW13") (pin "A") (pinfunction "1_A") (pintype "passive"))
      (node (ref "SW23") (pin "A") (pinfunction "1_A") (pintype "passive"))
      (node (ref "SW33") (pin "A") (pinfunction "1_A") (pintype "passive"))
      (node (ref "SW43") (pin "A") (pinfunction "1_A") (pintype "passive"))
      (node (ref "U$80") (pin "25") (pinfunction "PD4(ADC8)_25") (pintype "bidirectional"))
    )
    (net (code "30") (name "D5") (class "Default")
      (node (ref "SW02") (pin "A") (pinfunction "1_A") (pintype "passive"))
      (node (ref "SW12") (pin "A") (pinfunction "1_A") (pintype "passive"))
      (node (ref "SW22") (pin "A") (pinfunction "1_A") (pintype "passive"))
      (node (ref "SW32") (pin "A") (pinfunction "1_A") (pintype "passive"))
      (node (ref "SW42") (pin "A") (pinfunction "1_A") (pintype "passive"))
      (node (ref "U$80") (pin "22") (pinfunction "PD5_22") (pintype "bidirectional"))
    )
    (net (code "31") (name "D6") (class "Default")
      (node (ref "SW01") (pin "A") (pinfunction "1_A") (pintype "passive"))
      (node (ref "SW11") (pin "A") (pinfunction "1_A") (pintype "passive"))
      (node (ref "SW21") (pin "A") (pinfunction "1_A") (pintype "passive"))
      (node (ref "SW31") (pin "A") (pinfunction "1_A") (pintype "passive"))
      (node (ref "SW41") (pin "A") (pinfunction "1_A") (pintype "passive"))
      (node (ref "U$80") (pin "26") (pinfunction "PD6(ADC9)_26") (pintype "bidirectional"))
    )
    (net (code "32") (name "D7") (class "Default")
      (node (ref "SW00") (pin "A") (pinfunction "1_A") (pintype "passive"))
      (node (ref "SW10") (pin "A") (pinfunction "1_A") (pintype "passive"))
      (node (ref "SW20") (pin "A") (pinfunction "1_A") (pintype "passive"))
      (node (ref "SW30") (pin "A") (pinfunction "1_A") (pintype "passive"))
      (node (ref "U$34") (pin "B1B") (pinfunction "SEL-_B1B") (pintype "bidirectional"))
      (node (ref "U$34") (pin "B1B1") (pinfunction "SEL-_B1B1") (pintype "bidirectional"))
      (node (ref "U$34") (pin "B2B") (pinfunction "SEL-_B2B") (pintype "bidirectional"))
      (node (ref "U$34") (pin "B2B1") (pinfunction "SEL-_B2B1") (pintype "bidirectional"))
      (node (ref "U$80") (pin "27") (pinfunction "PD7(ADC10)_27") (pintype "bidirectional"))
    )
    (net (code "33") (name "D8") (class "Default")
      (node (ref "U$100") (pin "GND") (pinfunction "CAT_GND") (pintype "bidirectional"))
      (node (ref "U$104") (pin "GND") (pinfunction "CAT_GND") (pintype "bidirectional"))
      (node (ref "U$108") (pin "GND") (pinfunction "CAT_GND") (pintype "bidirectional"))
      (node (ref "U$135") (pin "GND") (pinfunction "CAT_GND") (pintype "bidirectional"))
      (node (ref "U$140") (pin "GND") (pinfunction "CAT_GND") (pintype "bidirectional"))
      (node (ref "U$18") (pin "GND") (pinfunction "CAT_GND") (pintype "bidirectional"))
      (node (ref "U$23") (pin "GND") (pinfunction "CAT_GND") (pintype "bidirectional"))
      (node (ref "U$30") (pin "GND") (pinfunction "CAT_GND") (pintype "bidirectional"))
      (node (ref "U$68") (pin "GND") (pinfunction "CAT_GND") (pintype "bidirectional"))
      (node (ref "U$95") (pin "GND") (pinfunction "CAT_GND") (pintype "bidirectional"))
    )
    (net (code "34") (name "D9") (class "Default")
      (node (ref "U$101") (pin "GND") (pinfunction "CAT_GND") (pintype "bidirectional"))
      (node (ref "U$105") (pin "GND") (pinfunction "CAT_GND") (pintype "bidirectional"))
      (node (ref "U$109") (pin "GND") (pinfunction "CAT_GND") (pintype "bidirectional"))
      (node (ref "U$136") (pin "GND") (pinfunction "CAT_GND") (pintype "bidirectional"))
      (node (ref "U$141") (pin "GND") (pinfunction "CAT_GND") (pintype "bidirectional"))
      (node (ref "U$19") (pin "GND") (pinfunction "CAT_GND") (pintype "bidirectional"))
      (node (ref "U$24") (pin "GND") (pinfunction "CAT_GND") (pintype "bidirectional"))
      (node (ref "U$31") (pin "GND") (pinfunction "CAT_GND") (pintype "bidirectional"))
      (node (ref "U$69") (pin "GND") (pinfunction "CAT_GND") (pintype "bidirectional"))
      (node (ref "U$96") (pin "GND") (pinfunction "CAT_GND") (pintype "bidirectional"))
    )
    (net (code "35") (name "D10") (class "Default")
      (node (ref "ROT3") (pin "SW+") (pinfunction "SW+_SW+") (pintype "bidirectional"))
      (node (ref "SW18") (pin "A") (pinfunction "1_A") (pintype "passive"))
      (node (ref "SW28") (pin "A") (pinfunction "1_A") (pintype "passive"))
      (node (ref "SW38") (pin "A") (pinfunction "1_A") (pintype "passive"))
      (node (ref "SW48") (pin "A") (pinfunction "1_A") (pintype "passive"))
    )
    (net (code "36") (name "D11") (class "Default")
      (node (ref "ROT2") (pin "SW+") (pinfunction "SW+_SW+") (pintype "bidirectional"))
      (node (ref "SW17") (pin "A") (pinfunction "1_A") (pintype "passive"))
      (node (ref "SW27") (pin "A") (pinfunction "1_A") (pintype "passive"))
      (node (ref "SW37") (pin "A") (pinfunction "1_A") (pintype "passive"))
      (node (ref "SW47") (pin "A") (pinfunction "1_A") (pintype "passive"))
    )
    (net (code "37") (name "D12") (class "Default")
      (node (ref "ROT1") (pin "SW+") (pinfunction "SW+_SW+") (pintype "bidirectional"))
      (node (ref "SW16") (pin "A") (pinfunction "1_A") (pintype "passive"))
      (node (ref "SW26") (pin "A") (pinfunction "1_A") (pintype "passive"))
      (node (ref "SW36") (pin "A") (pinfunction "1_A") (pintype "passive"))
      (node (ref "SW46") (pin "A") (pinfunction "1_A") (pintype "passive"))
    )
    (net (code "38") (name "D13") (class "Default")
      (node (ref "ROT0") (pin "SW+") (pinfunction "SW+_SW+") (pintype "bidirectional"))
      (node (ref "SW15") (pin "A") (pinfunction "1_A") (pintype "passive"))
      (node (ref "SW25") (pin "A") (pinfunction "1_A") (pintype "passive"))
      (node (ref "SW35") (pin "A") (pinfunction "1_A") (pintype "passive"))
      (node (ref "SW45") (pin "A") (pinfunction "1_A") (pintype "passive"))
    )
    (net (code "39") (name "D14") (class "Default")
      (node (ref "U$102") (pin "GND") (pinfunction "CAT_GND") (pintype "bidirectional"))
      (node (ref "U$106") (pin "GND") (pinfunction "CAT_GND") (pintype "bidirectional"))
      (node (ref "U$110") (pin "GND") (pinfunction "CAT_GND") (pintype "bidirectional"))
      (node (ref "U$137") (pin "GND") (pinfunction "CAT_GND") (pintype "bidirectional"))
      (node (ref "U$142") (pin "GND") (pinfunction "CAT_GND") (pintype "bidirectional"))
      (node (ref "U$20") (pin "GND") (pinfunction "CAT_GND") (pintype "bidirectional"))
      (node (ref "U$26") (pin "GND") (pinfunction "CAT_GND") (pintype "bidirectional"))
      (node (ref "U$33") (pin "GND") (pinfunction "CAT_GND") (pintype "bidirectional"))
      (node (ref "U$70") (pin "GND") (pinfunction "CAT_GND") (pintype "bidirectional"))
      (node (ref "U$97") (pin "GND") (pinfunction "CAT_GND") (pintype "bidirectional"))
    )
    (net (code "40") (name "D15") (class "Default")
      (node (ref "U$13") (pin "GND") (pinfunction "CAT_GND") (pintype "bidirectional"))
      (node (ref "U$14") (pin "GND") (pinfunction "CAT_GND") (pintype "bidirectional"))
      (node (ref "U$17") (pin "GND") (pinfunction "CAT_GND") (pintype "bidirectional"))
      (node (ref "U$21") (pin "GND") (pinfunction "CAT_GND") (pintype "bidirectional"))
      (node (ref "U$27") (pin "GND") (pinfunction "CAT_GND") (pintype "bidirectional"))
      (node (ref "U$29") (pin "GND") (pinfunction "CAT_GND") (pintype "bidirectional"))
      (node (ref "U$32") (pin "GND") (pinfunction "CAT_GND") (pintype "bidirectional"))
      (node (ref "U$54") (pin "GND") (pinfunction "CAT_GND") (pintype "bidirectional"))
      (node (ref "U$59") (pin "GND") (pinfunction "CAT_GND") (pintype "bidirectional"))
      (node (ref "U$63") (pin "GND") (pinfunction "CAT_GND") (pintype "bidirectional"))
    )
    (net (code "41") (name "D16") (class "Default")
      (node (ref "SW09") (pin "A") (pinfunction "1_A") (pintype "passive"))
      (node (ref "SW19") (pin "A") (pinfunction "1_A") (pintype "passive"))
      (node (ref "SW29") (pin "A") (pinfunction "1_A") (pintype "passive"))
      (node (ref "SW39") (pin "A") (pinfunction "1_A") (pintype "passive"))
      (node (ref "SW49") (pin "A") (pinfunction "1_A") (pintype "passive"))
    )
    (net (code "42") (name "D20") (class "Default")
      (node (ref "ROT3") (pin "A") (pinfunction "A_A") (pintype "bidirectional"))
    )
    (net (code "43") (name "D21") (class "Default")
      (node (ref "ROT3") (pin "B") (pinfunction "B_B") (pintype "bidirectional"))
    )
    (net (code "44") (name "D22") (class "Default")
      (node (ref "ROT1") (pin "B") (pinfunction "B_B") (pintype "bidirectional"))
    )
    (net (code "45") (name "D23") (class "Default")
      (node (ref "ROT1") (pin "A") (pinfunction "A_A") (pintype "bidirectional"))
    )
    (net (code "46") (name "D24") (class "Default")
      (node (ref "ROT0") (pin "A") (pinfunction "A_A") (pintype "bidirectional"))
    )
    (net (code "47") (name "D25") (class "Default")
      (node (ref "ROT0") (pin "B") (pinfunction "B_B") (pintype "bidirectional"))
    )
    (net (code "48") (name "D26") (class "Default")
      (node (ref "U$34") (pin "V2") (pinfunction "V_V2") (pintype "bidirectional"))
      (node (ref "U$34") (pin "VS2") (pinfunction "V_VS2") (pintype "bidirectional"))
    )
    (net (code "49") (name "D27") (class "Default")
      (node (ref "U$34") (pin "H2") (pinfunction "H_H2") (pintype "bidirectional"))
      (node (ref "U$34") (pin "HS2") (pinfunction "H_HS2") (pintype "bidirectional"))
    )
    (net (code "50") (name "D28") (class "Default")
      (node (ref "ROT2") (pin "A") (pinfunction "A_A") (pintype "bidirectional"))
    )
    (net (code "51") (name "D29") (class "Default")
      (node (ref "ROT2") (pin "B") (pinfunction "B_B") (pintype "bidirectional"))
    )
    (net (code "52") (name "GND") (class "Default")
      (node (ref "C17") (pin "2") (pinfunction "2_2") (pintype "passive"))
      (node (ref "C18") (pin "2") (pinfunction "2_2") (pintype "passive"))
      (node (ref "C19") (pin "2") (pinfunction "2_2") (pintype "passive"))
      (node (ref "C20") (pin "2") (pinfunction "2_2") (pintype "passive"))
      (node (ref "C21") (pin "2") (pinfunction "2_2") (pintype "passive"))
      (node (ref "J1") (pin "GND") (pinfunction "GND_GND") (pintype "bidirectional"))
      (node (ref "J1") (pin "GND2") (pinfunction "GND_GND2") (pintype "bidirectional"))
      (node (ref "JP2") (pin "6") (pinfunction "6_6") (pintype "passive"))
      (node (ref "R14") (pin "1") (pinfunction "1_1") (pintype "passive"))
      (node (ref "R15") (pin "1") (pinfunction "1_1") (pintype "passive"))
      (node (ref "ROT0") (pin "C") (pinfunction "C_C") (pintype "bidirectional"))
      (node (ref "ROT1") (pin "C") (pinfunction "C_C") (pintype "bidirectional"))
      (node (ref "ROT2") (pin "C") (pinfunction "C_C") (pintype "bidirectional"))
      (node (ref "ROT3") (pin "C") (pinfunction "C_C") (pintype "bidirectional"))
      (node (ref "RS1") (pin "1") (pinfunction "1_1") (pintype "passive"))
      (node (ref "U$34") (pin "H3") (pinfunction "H-_H3") (pintype "bidirectional"))
      (node (ref "U$34") (pin "HS3") (pinfunction "H-_HS3") (pintype "bidirectional"))
      (node (ref "U$34") (pin "V3") (pinfunction "V-_V3") (pintype "bidirectional"))
      (node (ref "U$34") (pin "VS3") (pinfunction "V-_VS3") (pintype "bidirectional"))
      (node (ref "U$80") (pin "15") (pinfunction "GND_15") (pintype "bidirectional"))
      (node (ref "U$80") (pin "23") (pinfunction "GND_23") (pintype "bidirectional"))
      (node (ref "U$80") (pin "33") (pinfunction "PE2/~{HWB}_33") (pintype "bidirectional"))
      (node (ref "U$80") (pin "35") (pinfunction "GND_35") (pintype "bidirectional"))
      (node (ref "U$80") (pin "43") (pinfunction "GND_43") (pintype "bidirectional"))
      (node (ref "U$80") (pin "5") (pinfunction "UGND_5") (pintype "bidirectional"))
    )
    (net (code "53") (name "Net-(J1-CC1)") (class "Default")
      (node (ref "J1") (pin "A5") (pinfunction "CC1_A5") (pintype "bidirectional"))
      (node (ref "R15") (pin "2") (pinfunction "2_2") (pintype "passive"))
    )
    (net (code "54") (name "Net-(J1-CC2)") (class "Default")
      (node (ref "J1") (pin "B5") (pinfunction "CC2_B5") (pintype "bidirectional"))
      (node (ref "R14") (pin "2") (pinfunction "2_2") (pintype "passive"))
    )
    (net (code "55") (name "Net-(SW00-2)") (class "Default")
      (node (ref "SW00") (pin "B") (pinfunction "2_B") (pintype "passive"))
      (node (ref "U$71") (pin "SIGNAL") (pinfunction "ANO_SIGNAL") (pintype "bidirectional"))
    )
    (net (code "56") (name "Net-(SW01-2)") (class "Default")
      (node (ref "SW01") (pin "B") (pinfunction "2_B") (pintype "passive"))
      (node (ref "U$94") (pin "SIGNAL") (pinfunction "ANO_SIGNAL") (pintype "bidirectional"))
    )
    (net (code "57") (name "Net-(SW02-2)") (class "Default")
      (node (ref "SW02") (pin "B") (pinfunction "2_B") (pintype "passive"))
      (node (ref "U$99") (pin "SIGNAL") (pinfunction "ANO_SIGNAL") (pintype "bidirectional"))
    )
    (net (code "58") (name "Net-(SW03-2)") (class "Default")
      (node (ref "SW03") (pin "B") (pinfunction "2_B") (pintype "passive"))
      (node (ref "U$103") (pin "SIGNAL") (pinfunction "ANO_SIGNAL") (pintype "bidirectional"))
    )
    (net (code "59") (name "Net-(SW04-2)") (class "Default")
      (node (ref "SW04") (pin "B") (pinfunction "2_B") (pintype "passive"))
      (node (ref "U$111") (pin "SIGNAL") (pinfunction "ANO_SIGNAL") (pintype "bidirectional"))
    )
    (net (code "60") (name "Net-(SW09-2)") (class "Default")
      (node (ref "SW09") (pin "B") (pinfunction "2_B") (pintype "passive"))
      (node (ref "U$28") (pin "SIGNAL") (pinfunction "ANO_SIGNAL") (pintype "bidirectional"))
    )
    (net (code "61") (name "Net-(SW10-2)") (class "Default")
      (node (ref "SW10") (pin "B") (pinfunction "2_B") (pintype "passive"))
      (node (ref "U$68") (pin "SIGNAL") (pinfunction "ANO_SIGNAL") (pintype "bidirectional"))
    )
    (net (code "62") (name "Net-(SW11-2)") (class "Default")
      (node (ref "SW11") (pin "B") (pinfunction "2_B") (pintype "passive"))
      (node (ref "U$95") (pin "SIGNAL") (pinfunction "ANO_SIGNAL") (pintype "bidirectional"))
    )
    (net (code "63") (name "Net-(SW12-2)") (class "Default")
      (node (ref "SW12") (pin "B") (pinfunction "2_B") (pintype "passive"))
      (node (ref "U$100") (pin "SIGNAL") (pinfunction "ANO_SIGNAL") (pintype "bidirectional"))
    )
    (net (code "64") (name "Net-(SW13-2)") (class "Default")
      (node (ref "SW13") (pin "B") (pinfunction "2_B") (pintype "passive"))
      (node (ref "U$104") (pin "SIGNAL") (pinfunction "ANO_SIGNAL") (pintype "bidirectional"))
    )
    (net (code "65") (name "Net-(SW14-2)") (class "Default")
      (node (ref "SW14") (pin "B") (pinfunction "2_B") (pintype "passive"))
      (node (ref "U$108") (pin "SIGNAL") (pinfunction "ANO_SIGNAL") (pintype "bidirectional"))
    )
    (net (code "66") (name "Net-(SW15-2)") (class "Default")
      (node (ref "SW15") (pin "B") (pinfunction "2_B") (pintype "passive"))
      (node (ref "U$135") (pin "SIGNAL") (pinfunction "ANO_SIGNAL") (pintype "bidirectional"))
    )
    (net (code "67") (name "Net-(SW16-2)") (class "Default")
      (node (ref "SW16") (pin "B") (pinfunction "2_B") (pintype "passive"))
      (node (ref "U$140") (pin "SIGNAL") (pinfunction "ANO_SIGNAL") (pintype "bidirectional"))
    )
    (net (code "68") (name "Net-(SW17-2)") (class "Default")
      (node (ref "SW17") (pin "B") (pinfunction "2_B") (pintype "passive"))
      (node (ref "U$18") (pin "SIGNAL") (pinfunction "ANO_SIGNAL") (pintype "bidirectional"))
    )
    (net (code "69") (name "Net-(SW18-2)") (class "Default")
      (node (ref "SW18") (pin "B") (pinfunction "2_B") (pintype "passive"))
      (node (ref "U$23") (pin "SIGNAL") (pinfunction "ANO_SIGNAL") (pintype "bidirectional"))
    )
    (net (code "70") (name "Net-(SW19-2)") (class "Default")
      (node (ref "SW19") (pin "B") (pinfunction "2_B") (pintype "passive"))
      (node (ref "U$30") (pin "SIGNAL") (pinfunction "ANO_SIGNAL") (pintype "bidirectional"))
    )
    (net (code "71") (name "Net-(SW20-2)") (class "Default")
      (node (ref "SW20") (pin "B") (pinfunction "2_B") (pintype "passive"))
      (node (ref "U$69") (pin "SIGNAL") (pinfunction "ANO_SIGNAL") (pintype "bidirectional"))
    )
    (net (code "72") (name "Net-(SW21-2)") (class "Default")
      (node (ref "SW21") (pin "B") (pinfunction "2_B") (pintype "passive"))
      (node (ref "U$96") (pin "SIGNAL") (pinfunction "ANO_SIGNAL") (pintype "bidirectional"))
    )
    (net (code "73") (name "Net-(SW22-2)") (class "Default")
      (node (ref "SW22") (pin "B") (pinfunction "2_B") (pintype "passive"))
      (node (ref "U$101") (pin "SIGNAL") (pinfunction "ANO_SIGNAL") (pintype "bidirectional"))
    )
    (net (code "74") (name "Net-(SW23-2)") (class "Default")
      (node (ref "SW23") (pin "B") (pinfunction "2_B") (pintype "passive"))
      (node (ref "U$105") (pin "SIGNAL") (pinfunction "ANO_SIGNAL") (pintype "bidirectional"))
    )
    (net (code "75") (name "Net-(SW24-2)") (class "Default")
      (node (ref "SW24") (pin "B") (pinfunction "2_B") (pintype "passive"))
      (node (ref "U$109") (pin "SIGNAL") (pinfunction "ANO_SIGNAL") (pintype "bidirectional"))
    )
    (net (code "76") (name "Net-(SW25-2)") (class "Default")
      (node (ref "SW25") (pin "B") (pinfunction "2_B") (pintype "passive"))
      (node (ref "U$136") (pin "SIGNAL") (pinfunction "ANO_SIGNAL") (pintype "bidirectional"))
    )
    (net (code "77") (name "Net-(SW26-2)") (class "Default")
      (node (ref "SW26") (pin "B") (pinfunction "2_B") (pintype "passive"))
      (node (ref "U$141") (pin "SIGNAL") (pinfunction "ANO_SIGNAL") (pintype "bidirectional"))
    )
    (net (code "78") (name "Net-(SW27-2)") (class "Default")
      (node (ref "SW27") (pin "B") (pinfunction "2_B") (pintype "passive"))
      (node (ref "U$19") (pin "SIGNAL") (pinfunction "ANO_SIGNAL") (pintype "bidirectional"))
    )
    (net (code "79") (name "Net-(SW28-2)") (class "Default")
      (node (ref "SW28") (pin "B") (pinfunction "2_B") (pintype "passive"))
      (node (ref "U$24") (pin "SIGNAL") (pinfunction "ANO_SIGNAL") (pintype "bidirectional"))
    )
    (net (code "80") (name "Net-(SW29-2)") (class "Default")
      (node (ref "SW29") (pin "B") (pinfunction "2_B") (pintype "passive"))
      (node (ref "U$31") (pin "SIGNAL") (pinfunction "ANO_SIGNAL") (pintype "bidirectional"))
    )
    (net (code "81") (name "Net-(SW30-2)") (class "Default")
      (node (ref "SW30") (pin "B") (pinfunction "2_B") (pintype "passive"))
      (node (ref "U$70") (pin "SIGNAL") (pinfunction "ANO_SIGNAL") (pintype "bidirectional"))
    )
    (net (code "82") (name "Net-(SW31-2)") (class "Default")
      (node (ref "SW31") (pin "B") (pinfunction "2_B") (pintype "passive"))
      (node (ref "U$97") (pin "SIGNAL") (pinfunction "ANO_SIGNAL") (pintype "bidirectional"))
    )
    (net (code "83") (name "Net-(SW32-2)") (class "Default")
      (node (ref "SW32") (pin "B") (pinfunction "2_B") (pintype "passive"))
      (node (ref "U$102") (pin "SIGNAL") (pinfunction "ANO_SIGNAL") (pintype "bidirectional"))
    )
    (net (code "84") (name "Net-(SW33-2)") (class "Default")
      (node (ref "SW33") (pin "B") (pinfunction "2_B") (pintype "passive"))
      (node (ref "U$106") (pin "SIGNAL") (pinfunction "ANO_SIGNAL") (pintype "bidirectional"))
    )
    (net (code "85") (name "Net-(SW34-2)") (class "Default")
      (node (ref "SW34") (pin "B") (pinfunction "2_B") (pintype "passive"))
      (node (ref "U$110") (pin "SIGNAL") (pinfunction "ANO_SIGNAL") (pintype "bidirectional"))
    )
    (net (code "86") (name "Net-(SW35-2)") (class "Default")
      (node (ref "SW35") (pin "B") (pinfunction "2_B") (pintype "passive"))
      (node (ref "U$137") (pin "SIGNAL") (pinfunction "ANO_SIGNAL") (pintype "bidirectional"))
    )
    (net (code "87") (name "Net-(SW36-2)") (class "Default")
      (node (ref "SW36") (pin "B") (pinfunction "2_B") (pintype "passive"))
      (node (ref "U$142") (pin "SIGNAL") (pinfunction "ANO_SIGNAL") (pintype "bidirectional"))
    )
    (net (code "88") (name "Net-(SW37-2)") (class "Default")
      (node (ref "SW37") (pin "B") (pinfunction "2_B") (pintype "passive"))
      (node (ref "U$20") (pin "SIGNAL") (pinfunction "ANO_SIGNAL") (pintype "bidirectional"))
    )
    (net (code "89") (name "Net-(SW38-2)") (class "Default")
      (node (ref "SW38") (pin "B") (pinfunction "2_B") (pintype "passive"))
      (node (ref "U$26") (pin "SIGNAL") (pinfunction "ANO_SIGNAL") (pintype "bidirectional"))
    )
    (net (code "90") (name "Net-(SW39-2)") (class "Default")
      (node (ref "SW39") (pin "B") (pinfunction "2_B") (pintype "passive"))
      (node (ref "U$33") (pin "SIGNAL") (pinfunction "ANO_SIGNAL") (pintype "bidirectional"))
    )
    (net (code "91") (name "Net-(SW41-2)") (class "Default")
      (node (ref "SW41") (pin "B") (pinfunction "2_B") (pintype "passive"))
      (node (ref "U$17") (pin "SIGNAL") (pinfunction "ANO_SIGNAL") (pintype "bidirectional"))
    )
    (net (code "92") (name "Net-(SW42-2)") (class "Default")
      (node (ref "SW42") (pin "B") (pinfunction "2_B") (pintype "passive"))
      (node (ref "U$21") (pin "SIGNAL") (pinfunction "ANO_SIGNAL") (pintype "bidirectional"))
    )
    (net (code "93") (name "Net-(SW43-2)") (class "Default")
      (node (ref "SW43") (pin "B") (pinfunction "2_B") (pintype "passive"))
      (node (ref "U$29") (pin "SIGNAL") (pinfunction "ANO_SIGNAL") (pintype "bidirectional"))
    )
    (net (code "94") (name "Net-(SW44-2)") (class "Default")
      (node (ref "SW44") (pin "B") (pinfunction "2_B") (pintype "passive"))
      (node (ref "U$54") (pin "SIGNAL") (pinfunction "ANO_SIGNAL") (pintype "bidirectional"))
    )
    (net (code "95") (name "Net-(SW45-2)") (class "Default")
      (node (ref "SW45") (pin "B") (pinfunction "2_B") (pintype "passive"))
      (node (ref "U$59") (pin "SIGNAL") (pinfunction "ANO_SIGNAL") (pintype "bidirectional"))
    )
    (net (code "96") (name "Net-(SW46-2)") (class "Default")
      (node (ref "SW46") (pin "B") (pinfunction "2_B") (pintype "passive"))
      (node (ref "U$63") (pin "SIGNAL") (pinfunction "ANO_SIGNAL") (pintype "bidirectional"))
    )
    (net (code "97") (name "Net-(SW47-2)") (class "Default")
      (node (ref "SW47") (pin "B") (pinfunction "2_B") (pintype "passive"))
      (node (ref "U$13") (pin "SIGNAL") (pinfunction "ANO_SIGNAL") (pintype "bidirectional"))
    )
    (net (code "98") (name "Net-(SW48-2)") (class "Default")
      (node (ref "SW48") (pin "B") (pinfunction "2_B") (pintype "passive"))
      (node (ref "U$14") (pin "SIGNAL") (pinfunction "ANO_SIGNAL") (pintype "bidirectional"))
    )
    (net (code "99") (name "Net-(SW49-2)") (class "Default")
      (node (ref "SW49") (pin "B") (pinfunction "2_B") (pintype "passive"))
      (node (ref "U$27") (pin "SIGNAL") (pinfunction "ANO_SIGNAL") (pintype "bidirectional"))
    )
    (net (code "100") (name "Net-(U$15-ANO)") (class "Default")
      (node (ref "ROT2") (pin "SW-") (pinfunction "SW-_SW-") (pintype "bidirectional"))
      (node (ref "U$15") (pin "SIGNAL") (pinfunction "ANO_SIGNAL") (pintype "bidirectional"))
    )
    (net (code "101") (name "Net-(U$22-ANO)") (class "Default")
      (node (ref "ROT3") (pin "SW-") (pinfunction "SW-_SW-") (pintype "bidirectional"))
      (node (ref "U$22") (pin "SIGNAL") (pinfunction "ANO_SIGNAL") (pintype "bidirectional"))
    )
    (net (code "102") (name "Net-(U$32-ANO)") (class "Default")
      (node (ref "U$32") (pin "SIGNAL") (pinfunction "ANO_SIGNAL") (pintype "bidirectional"))
      (node (ref "U$34") (pin "B1A") (pinfunction "SEL+_B1A") (pintype "bidirectional"))
      (node (ref "U$34") (pin "B1A1") (pinfunction "SEL+_B1A1") (pintype "bidirectional"))
      (node (ref "U$34") (pin "B2A") (pinfunction "SEL+_B2A") (pintype "bidirectional"))
      (node (ref "U$34") (pin "B2A1") (pinfunction "SEL+_B2A1") (pintype "bidirectional"))
    )
    (net (code "103") (name "Net-(U$80-UCAP)") (class "Default")
      (node (ref "C17") (pin "1") (pinfunction "1_1") (pintype "passive"))
      (node (ref "U$80") (pin "6") (pinfunction "UCAP_6") (pintype "bidirectional"))
    )
    (net (code "104") (name "Net-(U$80-XTAL1)") (class "Default")
      (node (ref "C18") (pin "1") (pinfunction "1_1") (pintype "passive"))
      (node (ref "U$80") (pin "17") (pinfunction "XTAL1_17") (pintype "bidirectional"))
      (node (ref "Y2") (pin "P3") (pinfunction "2_P3") (pintype "passive"))
    )
    (net (code "105") (name "Net-(U$80-XTAL2)") (class "Default")
      (node (ref "C19") (pin "1") (pinfunction "1_1") (pintype "passive"))
      (node (ref "U$80") (pin "16") (pinfunction "XTAL2_16") (pintype "bidirectional"))
      (node (ref "Y2") (pin "P1") (pinfunction "1_P1") (pintype "passive"))
    )
    (net (code "106") (name "Net-(U$134-ANO)") (class "Default")
      (node (ref "ROT0") (pin "SW-") (pinfunction "SW-_SW-") (pintype "bidirectional"))
      (node (ref "U$134") (pin "SIGNAL") (pinfunction "ANO_SIGNAL") (pintype "bidirectional"))
    )
    (net (code "107") (name "Net-(U$139-ANO)") (class "Default")
      (node (ref "ROT1") (pin "SW-") (pinfunction "SW-_SW-") (pintype "bidirectional"))
      (node (ref "U$139") (pin "SIGNAL") (pinfunction "ANO_SIGNAL") (pintype "bidirectional"))
    )
    (net (code "108") (name "SHLD") (class "Default")
      (node (ref "J1") (pin "SHLD1") (pinfunction "SHLD_SHLD1") (pintype "bidirectional"))
      (node (ref "J1") (pin "SHLD2") (pinfunction "SHLD_SHLD2") (pintype "bidirectional"))
      (node (ref "J1") (pin "SHLD3") (pinfunction "SHLD_SHLD3") (pintype "bidirectional"))
      (node (ref "J1") (pin "SHLD4") (pinfunction "SHLD_SHLD4") (pintype "bidirectional"))
      (node (ref "J1") (pin "SHLD5") (pinfunction "SHLD_SHLD5") (pintype "bidirectional"))
      (node (ref "J1") (pin "SHLD6") (pinfunction "SHLD_SHLD6") (pintype "bidirectional"))
      (node (ref "J1") (pin "SHLD7") (pinfunction "SHLD_SHLD7") (pintype "bidirectional"))
      (node (ref "J1") (pin "SHLD8") (pinfunction "SHLD_SHLD8") (pintype "bidirectional"))
    )
    (net (code "109") (name "VBUS") (class "Default")
      (node (ref "D1") (pin "ANO") (pinfunction "ANO_ANO") (pintype "bidirectional"))
      (node (ref "J1") (pin "VBUS1") (pinfunction "VBUS_VBUS1") (pintype "bidirectional"))
      (node (ref "J1") (pin "VBUS2") (pinfunction "VBUS_VBUS2") (pintype "bidirectional"))
    )
  )
)
